# lathe_mainboard.net
KiCad netlist of a schematic drawn in Altium Designer
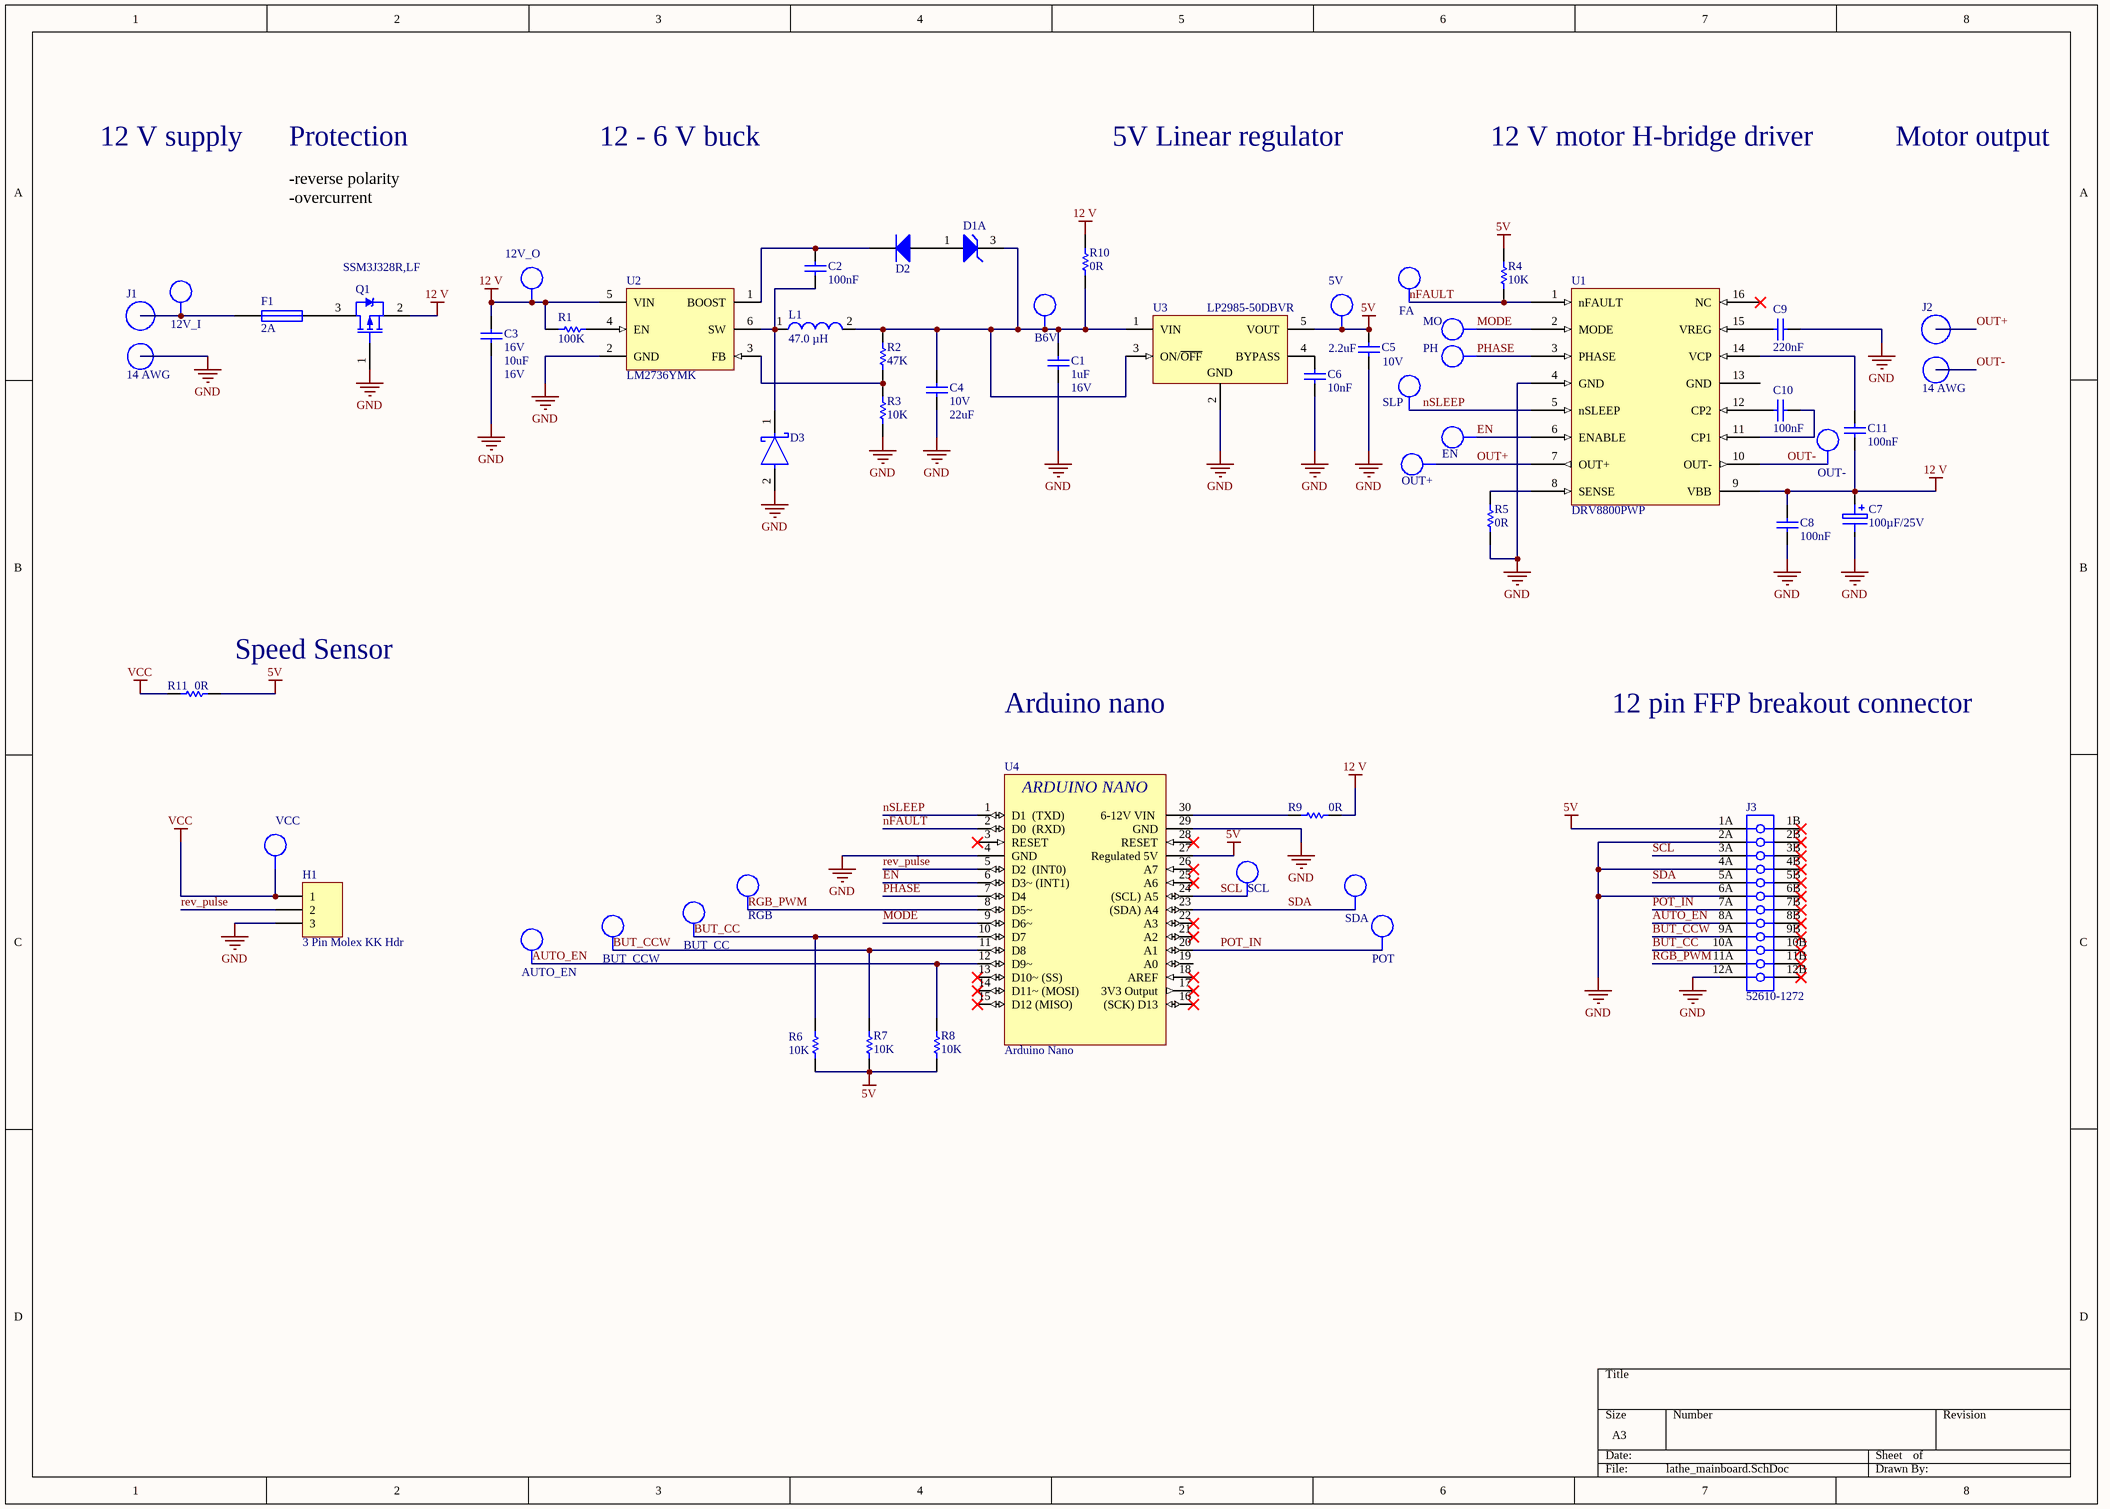
[diagram p0: lathe_mainboard.SchDoc]

(export (version "E")
  (design (tool "Eeschema 10.0.6"))
  (components
    (comp (ref "5V")
      (value "TP")
      (footprint "TP_1206")
      (description "Test-Point 3.3x1.6x2.1mm SMD")
      (fields
        (field (name "MANUFACTURER") "Harwin Inc")
        (field (name "MANUFACTURER PART NUMBER") "S1751-46R")
      )
      (libsource (lib "ECE AD19Components_22V1") (part "TP_1206"))
    )
    (comp (ref "12V_I")
      (value "TP")
      (footprint "TP_1206")
      (description "Test-Point 3.3x1.6x2.1mm SMD")
      (fields
        (field (name "MANUFACTURER") "Harwin Inc")
        (field (name "MANUFACTURER PART NUMBER") "S1751-46R")
      )
      (libsource (lib "ECE AD19Components_22V1") (part "TP_1206"))
    )
    (comp (ref "12V_O")
      (value "TP")
      (footprint "TP_1206")
      (description "Test-Point 3.3x1.6x2.1mm SMD")
      (fields
        (field (name "MANUFACTURER") "Harwin Inc")
        (field (name "MANUFACTURER PART NUMBER") "S1751-46R")
      )
      (libsource (lib "ECE AD19Components_22V1") (part "TP_1206"))
    )
    (comp (ref "AUTO_EN")
      (value "TP")
      (footprint "TP_1206")
      (description "Test-Point 3.3x1.6x2.1mm SMD")
      (fields
        (field (name "MANUFACTURER") "Harwin Inc")
        (field (name "MANUFACTURER PART NUMBER") "S1751-46R")
      )
      (libsource (lib "ECE AD19Components_22V1") (part "TP_1206"))
    )
    (comp (ref "B6V")
      (value "TP")
      (footprint "TP_1206")
      (description "Test-Point 3.3x1.6x2.1mm SMD")
      (fields
        (field (name "MANUFACTURER") "Harwin Inc")
        (field (name "MANUFACTURER PART NUMBER") "S1751-46R")
      )
      (libsource (lib "ECE AD19Components_22V1") (part "TP_1206"))
    )
    (comp (ref "BUT_CC")
      (value "TP")
      (footprint "TP_1206")
      (description "Test-Point 3.3x1.6x2.1mm SMD")
      (fields
        (field (name "MANUFACTURER") "Harwin Inc")
        (field (name "MANUFACTURER PART NUMBER") "S1751-46R")
      )
      (libsource (lib "ECE AD19Components_22V1") (part "TP_1206"))
    )
    (comp (ref "BUT_CCW")
      (value "TP")
      (footprint "TP_1206")
      (description "Test-Point 3.3x1.6x2.1mm SMD")
      (fields
        (field (name "MANUFACTURER") "Harwin Inc")
        (field (name "MANUFACTURER PART NUMBER") "S1751-46R")
      )
      (libsource (lib "ECE AD19Components_22V1") (part "TP_1206"))
    )
    (comp (ref "C1")
      (value "1uF")
      (footprint "CAPC1608L")
      (description "CAP CER 1uF Y5V -20% +80% 16V 0603")
      (fields (field (name "MAX VOLTAGE") "16V"))
      (libsource (lib "ECE AD19Components_22V1") (part "CC_1uF_0603"))
    )
    (comp (ref "C2")
      (value "100nF")
      (footprint "CAPC1608L")
      (description "CAP CER 100nF X7R +-10% 50V 0603")
      (libsource (lib "ECE AD19Components_22V1") (part "CC_100nF_0603"))
    )
    (comp (ref "C3")
      (value "10uF")
      (footprint "CAPC2012L")
      (description "CAP CER 10uF X5R 16V 0805")
      (fields
        (field (name "MANUFACTURER") "Samsung Electro-Mechanics")
        (field (name "MANUFACTURER PART NUMBER") "CL21A106KOQNNWE")
        (field (name "VOLTAGE - RATED") "16V")
        (field (name "MAX VOLTAGE") "16V")
      )
      (libsource (lib "ECE AD19Components_22V1") (part "CC_10uF_0805_16V"))
    )
    (comp (ref "C4")
      (value "22uF")
      (footprint "CAPC3216L")
      (description "CAP CER 22uF Y5V -20% +80% 10V 1206")
      (fields (field (name "MAX VOLTAGE") "10V"))
      (libsource (lib "ECE AD19Components_22V1") (part "CC_22uF_1206"))
    )
    (comp (ref "C5")
      (value "2.2uF")
      (footprint "CAPC1608L")
      (description "CAP CER 2.2uF X5R +-20% 10V 0603")
      (fields (field (name "MAX VOLTAGE") "10V"))
      (libsource (lib "ECE AD19Components_22V1") (part "CC_2.2uF_0603"))
    )
    (comp (ref "C6")
      (value "10nF")
      (footprint "CAPC1608L")
      (description "CAP CER 10nF X7R +-10% 50V 0603")
      (libsource (lib "ECE AD19Components_22V1") (part "CC_10nF_0603"))
    )
    (comp (ref "C7")
      (value "100µF/25V")
      (footprint "CAPAE6666X77M")
      (description "CAP ALUM 100UF 25V 20% SMD")
      (fields
        (field (name "MANUFACTURER") "Nichicon")
        (field (name "MANUFACTURER PART NUMBER") "UWT1E101MCL1GS")
        (field (name "CAPACITANCE") "100µF/25V")
      )
      (libsource (lib "ECE AD19Components_22V1") (part "CA_100uF_25V"))
    )
    (comp (ref "C8")
      (value "100nF")
      (footprint "CAPC1608L")
      (description "CAP CER 100nF X7R +-10% 50V 0603")
      (libsource (lib "ECE AD19Components_22V1") (part "CC_100nF_0603"))
    )
    (comp (ref "C9")
      (value "220nF")
      (footprint "CAPC1608L")
      (description "CAP CER 220nF Y5V -20% +80% 25V 0603")
      (libsource (lib "ECE AD19Components_22V1") (part "CC_220nF_0603"))
    )
    (comp (ref "C10")
      (value "100nF")
      (footprint "CAPC1608L")
      (description "CAP CER 100nF X7R +-10% 50V 0603")
      (libsource (lib "ECE AD19Components_22V1") (part "CC_100nF_0603"))
    )
    (comp (ref "C11")
      (value "100nF")
      (footprint "CAPC1608L")
      (description "CAP CER 100nF X7R +-10% 50V 0603")
      (libsource (lib "ECE AD19Components_22V1") (part "CC_100nF_0603"))
    )
    (comp (ref "D1")
      (value "BZX84C4V3LT1G")
      (footprint "ONSC-SOT-23-3-318-08_V")
      (description "Zener Voltage Regulator, 225 mW, 3-Pin SOT-23, Pb-Free, Tape and Reel")
      (fields (field (name "MANUFACTURER") "On Semiconductor"))
      (libsource (lib "Altium Content Vault") (part "ONSC-A1K3-3"))
    )
    (comp (ref "D2")
      (value "1N4148W-7-F")
      (footprint "DIOD-SOD123-2_V")
      (description "Fast Switching Diode, 100 V, 0.15 A, -65 to 150 degC, 2-Pin?SOD123, RoHS, Tape and Reel")
      (fields (field (name "MANUFACTURER") "DiodesIncorporated"))
      (libsource (lib "Altium Content Vault") (part "D-AK-2"))
    )
    (comp (ref "D3")
      (value "MSS1P3L-M3/89A")
      (footprint "FP-96591-MFG")
      (description "DIODE SCHOTTKY 30V 1A MICROSMP")
      (fields
        (field (name "OCTOPART") "https://octopart.com/mss1p3l-m3%2F89a-vishay-42670898")
        (field (name "MANUFACTURER") "Vishay")
      )
      (libsource (lib "Altium Content Vault") (part "1d6ec82d83fb6aee721767c19dac4b9"))
    )
    (comp (ref "EN")
      (value "TP")
      (footprint "TP_1206")
      (description "Test-Point 3.3x1.6x2.1mm SMD")
      (fields
        (field (name "MANUFACTURER") "Harwin Inc")
        (field (name "MANUFACTURER PART NUMBER") "S1751-46R")
      )
      (libsource (lib "ECE AD19Components_22V1") (part "TP_1206"))
    )
    (comp (ref "F1")
      (value "2A")
      (footprint "RESC3216N")
      (description "Fuse 2.0A Very Fast Acting 1206 SMD")
      (fields
        (field (name "MANUFACTURER") "MULTICOMP")
        (field (name "MANUFACTURER PART NUMBER") "MC12CF 002")
      )
      (libsource (lib "ECE AD19Components_22V1") (part "FS_Fuse_2.0A"))
    )
    (comp (ref "FA")
      (value "TP")
      (footprint "TP_1206")
      (description "Test-Point 3.3x1.6x2.1mm SMD")
      (fields
        (field (name "MANUFACTURER") "Harwin Inc")
        (field (name "MANUFACTURER PART NUMBER") "S1751-46R")
      )
      (libsource (lib "ECE AD19Components_22V1") (part "TP_1206"))
    )
    (comp (ref "H1")
      (value "3 Pin Molex KK Hdr")
      (footprint "MOLEX_KK_3_HDR")
      (description "CONN HEADER 3POS 2.54mm VERT_Thru Hole")
      (fields (field (name "MANUFACTURER") "Molex"))
      (libsource (lib "ECE AD19Components_22V1") (part "JA_MOLEX_KK_3POS"))
    )
    (comp (ref "J1")
      (value "14 AWG")
      (footprint "14AWG_holes")
      (libsource (lib "lathe_library") (part "14AWG_holle"))
    )
    (comp (ref "J2")
      (value "14 AWG")
      (footprint "14AWG_holes")
      (libsource (lib "lathe_library") (part "14AWG_holle"))
    )
    (comp (ref "J3")
      (value "52610-1272")
      (footprint "MOLX-52610-1272")
      (fields (field (name "MANUFACTURER") "Molex"))
      (libsource (lib "Altium Content Vault") (part "MOLX-52610-1272"))
    )
    (comp (ref "L1")
      (value "47.0 µH")
      (footprint "WE-PD-L")
      (description "SMD-Shielded Power Inductor WE-PD, L = 47.0 µH")
      (libsource (lib "Altium Content Vault") (part "PAS-IND-INDUCTOR-2"))
    )
    (comp (ref "MO")
      (value "TP")
      (footprint "TP_1206")
      (description "Test-Point 3.3x1.6x2.1mm SMD")
      (fields
        (field (name "MANUFACTURER") "Harwin Inc")
        (field (name "MANUFACTURER PART NUMBER") "S1751-46R")
      )
      (libsource (lib "ECE AD19Components_22V1") (part "TP_1206"))
    )
    (comp (ref "OUT+")
      (value "TP")
      (footprint "TP_1206")
      (description "Test-Point 3.3x1.6x2.1mm SMD")
      (fields
        (field (name "MANUFACTURER") "Harwin Inc")
        (field (name "MANUFACTURER PART NUMBER") "S1751-46R")
      )
      (libsource (lib "ECE AD19Components_22V1") (part "TP_1206"))
    )
    (comp (ref "OUT-")
      (value "TP")
      (footprint "TP_1206")
      (description "Test-Point 3.3x1.6x2.1mm SMD")
      (fields
        (field (name "MANUFACTURER") "Harwin Inc")
        (field (name "MANUFACTURER PART NUMBER") "S1751-46R")
      )
      (libsource (lib "ECE AD19Components_22V1") (part "TP_1206"))
    )
    (comp (ref "PH")
      (value "TP")
      (footprint "TP_1206")
      (description "Test-Point 3.3x1.6x2.1mm SMD")
      (fields
        (field (name "MANUFACTURER") "Harwin Inc")
        (field (name "MANUFACTURER PART NUMBER") "S1751-46R")
      )
      (libsource (lib "ECE AD19Components_22V1") (part "TP_1206"))
    )
    (comp (ref "POT")
      (value "TP")
      (footprint "TP_1206")
      (description "Test-Point 3.3x1.6x2.1mm SMD")
      (fields
        (field (name "MANUFACTURER") "Harwin Inc")
        (field (name "MANUFACTURER PART NUMBER") "S1751-46R")
      )
      (libsource (lib "ECE AD19Components_22V1") (part "TP_1206"))
    )
    (comp (ref "Q1")
      (value "SSM3J328R,LF")
      (footprint "SOT23_L")
      (description "MOSFET P-CH 20V 6A SOT23-3")
      (fields
        (field (name "MANUFACTURER") "Toshiba")
        (field (name "MANUFACTURER PART NUMBER") "SSM3J328R,LF")
      )
      (libsource (lib "ECE AD19Components_22V1") (part "TM_SSM3J328R"))
    )
    (comp (ref "R1")
      (value "100K")
      (footprint "RESC1608L")
      (description "RES 100K OHM 1/10W 5% 0603 SMD")
      (libsource (lib "ECE AD19Components_22V1") (part "RS_100K"))
    )
    (comp (ref "R2")
      (value "47K")
      (footprint "RESC1608N")
      (description "RES 47.0K OHM 1/10W 5% 0603 SMD")
      (libsource (lib "ECE AD19Components_22V1") (part "RS_47K"))
    )
    (comp (ref "R3")
      (value "10K")
      (footprint "RESC1608L")
      (description "RES 10.0K OHM 1/10W 5% 0603 SMD")
      (libsource (lib "ECE AD19Components_22V1") (part "RS_10K"))
    )
    (comp (ref "R4")
      (value "10K")
      (footprint "RESC1608L")
      (description "RES 10.0K OHM 1/10W 5% 0603 SMD")
      (libsource (lib "ECE AD19Components_22V1") (part "RS_10K"))
    )
    (comp (ref "R5")
      (value "0R")
      (footprint "RESC1608L")
      (description "RES 0.0 OHM 1/10W 5% 0603 SMD")
      (libsource (lib "ECE AD19Components_22V1") (part "RS_0R0"))
    )
    (comp (ref "R6")
      (value "10K")
      (footprint "RESC1608L")
      (description "RES 10.0K OHM 1/10W 5% 0603 SMD")
      (libsource (lib "ECE AD19Components_22V1") (part "RS_10K"))
    )
    (comp (ref "R7")
      (value "10K")
      (footprint "RESC1608L")
      (description "RES 10.0K OHM 1/10W 5% 0603 SMD")
      (libsource (lib "ECE AD19Components_22V1") (part "RS_10K"))
    )
    (comp (ref "R8")
      (value "10K")
      (footprint "RESC1608L")
      (description "RES 10.0K OHM 1/10W 5% 0603 SMD")
      (libsource (lib "ECE AD19Components_22V1") (part "RS_10K"))
    )
    (comp (ref "R9")
      (value "0R")
      (footprint "RESC1608L")
      (description "RES 0.0 OHM 1/10W 5% 0603 SMD")
      (libsource (lib "ECE AD19Components_22V1") (part "RS_0R0"))
    )
    (comp (ref "R10")
      (value "0R")
      (footprint "RESC1608L")
      (description "RES 0.0 OHM 1/10W 5% 0603 SMD")
      (libsource (lib "ECE AD19Components_22V1") (part "RS_0R0"))
    )
    (comp (ref "R11")
      (value "0R")
      (footprint "RESC1608L")
      (description "RES 0.0 OHM 1/10W 5% 0603 SMD")
      (libsource (lib "ECE AD19Components_22V1") (part "RS_0R0"))
    )
    (comp (ref "RGB")
      (value "TP")
      (footprint "TP_1206")
      (description "Test-Point 3.3x1.6x2.1mm SMD")
      (fields
        (field (name "MANUFACTURER") "Harwin Inc")
        (field (name "MANUFACTURER PART NUMBER") "S1751-46R")
      )
      (libsource (lib "ECE AD19Components_22V1") (part "TP_1206"))
    )
    (comp (ref "SCL")
      (value "TP")
      (footprint "TP_1206")
      (description "Test-Point 3.3x1.6x2.1mm SMD")
      (fields
        (field (name "MANUFACTURER") "Harwin Inc")
        (field (name "MANUFACTURER PART NUMBER") "S1751-46R")
      )
      (libsource (lib "ECE AD19Components_22V1") (part "TP_1206"))
    )
    (comp (ref "SDA")
      (value "TP")
      (footprint "TP_1206")
      (description "Test-Point 3.3x1.6x2.1mm SMD")
      (fields
        (field (name "MANUFACTURER") "Harwin Inc")
        (field (name "MANUFACTURER PART NUMBER") "S1751-46R")
      )
      (libsource (lib "ECE AD19Components_22V1") (part "TP_1206"))
    )
    (comp (ref "SLP")
      (value "TP")
      (footprint "TP_1206")
      (description "Test-Point 3.3x1.6x2.1mm SMD")
      (fields
        (field (name "MANUFACTURER") "Harwin Inc")
        (field (name "MANUFACTURER PART NUMBER") "S1751-46R")
      )
      (libsource (lib "ECE AD19Components_22V1") (part "TP_1206"))
    )
    (comp (ref "U1")
      (value "DRV8800PWP")
      (footprint "SOP65P640X120-17N")
      (description "IC MTR DRV BIPOLR 8-38V 16HTSSOP")
      (libsource (lib "lathe_library") (part "DRV8800PWP"))
    )
    (comp (ref "U2")
      (value "LM2736YMK")
      (footprint "DDC0006A_L")
      (description "750mA Load Step-Down DC-DC Regulator, 6-pin Tiny SOT23")
      (fields (field (name "MANUFACTURER") "Texas Instruments"))
      (libsource (lib "Altium Content Vault") (part "PM-DCDC-LM2736MK"))
    )
    (comp (ref "U3")
      (value "LP2985-50DBVR")
      (footprint "DBV0005A_M")
      (fields (field (name "MANUFACTURER") "Texas Instruments"))
      (libsource (lib "lathe_library") (part "LP2985-50DBVR"))
    )
    (comp (ref "U4")
      (value "Arduino Nano")
      (footprint "Arduino-nano")
      (libsource (lib "ECE AD19Components_22V1") (part "Arduino Nano"))
    )
    (comp (ref "VCC")
      (value "TP")
      (footprint "TP_1206")
      (description "Test-Point 3.3x1.6x2.1mm SMD")
      (fields
        (field (name "MANUFACTURER") "Harwin Inc")
        (field (name "MANUFACTURER PART NUMBER") "S1751-46R")
      )
      (libsource (lib "ECE AD19Components_22V1") (part "TP_1206"))
    )
  )
  (nets
    (net (code "1") (name "/AUTO_EN") (class "Default")
      (node (ref "AUTO_EN") (pin "1") (pinfunction "1_1") (pintype "passive"))
      (node (ref "J3") (pin "8A") (pinfunction "8A_8A") (pintype "passive"))
      (node (ref "R8") (pin "2") (pinfunction "2_2") (pintype "passive"))
      (node (ref "U4") (pin "12") (pinfunction "D9~_12") (pintype "bidirectional"))
    )
    (net (code "2") (name "/BUT_CC") (class "Default")
      (node (ref "BUT_CC") (pin "1") (pinfunction "1_1") (pintype "passive"))
      (node (ref "J3") (pin "10A") (pinfunction "10A_10A") (pintype "passive"))
      (node (ref "R6") (pin "2") (pinfunction "2_2") (pintype "passive"))
      (node (ref "U4") (pin "10") (pinfunction "D7_10") (pintype "bidirectional"))
    )
    (net (code "3") (name "/BUT_CCW") (class "Default")
      (node (ref "BUT_CCW") (pin "1") (pinfunction "1_1") (pintype "passive"))
      (node (ref "J3") (pin "9A") (pinfunction "9A_9A") (pintype "passive"))
      (node (ref "R7") (pin "2") (pinfunction "2_2") (pintype "passive"))
      (node (ref "U4") (pin "11") (pinfunction "D8_11") (pintype "bidirectional"))
    )
    (net (code "4") (name "/EN") (class "Default")
      (node (ref "EN") (pin "1") (pinfunction "1_1") (pintype "passive"))
      (node (ref "U1") (pin "6") (pinfunction "ENABLE_6") (pintype "input"))
      (node (ref "U4") (pin "6") (pinfunction "D3~_(INT1)_6") (pintype "bidirectional"))
    )
    (net (code "5") (name "/MODE") (class "Default")
      (node (ref "MO") (pin "1") (pinfunction "1_1") (pintype "passive"))
      (node (ref "U1") (pin "2") (pinfunction "MODE_2") (pintype "input"))
      (node (ref "U4") (pin "9") (pinfunction "D6~_9") (pintype "bidirectional"))
    )
    (net (code "6") (name "/OUT+") (class "Default")
      (node (ref "J2") (pin "1") (pinfunction "1_1") (pintype "passive"))
      (node (ref "OUT+") (pin "1") (pinfunction "1_1") (pintype "passive"))
      (node (ref "U1") (pin "7") (pinfunction "OUT+_7") (pintype "output"))
    )
    (net (code "7") (name "/OUT-") (class "Default")
      (node (ref "J2") (pin "2") (pinfunction "2_2") (pintype "passive"))
      (node (ref "OUT-") (pin "1") (pinfunction "1_1") (pintype "passive"))
      (node (ref "U1") (pin "10") (pinfunction "OUT-_10") (pintype "output"))
    )
    (net (code "8") (name "/PHASE") (class "Default")
      (node (ref "PH") (pin "1") (pinfunction "1_1") (pintype "passive"))
      (node (ref "U1") (pin "3") (pinfunction "PHASE_3") (pintype "input"))
      (node (ref "U4") (pin "7") (pinfunction "D4_7") (pintype "bidirectional"))
    )
    (net (code "9") (name "/POT_IN") (class "Default")
      (node (ref "J3") (pin "7A") (pinfunction "7A_7A") (pintype "passive"))
      (node (ref "POT") (pin "1") (pinfunction "1_1") (pintype "passive"))
      (node (ref "U4") (pin "20") (pinfunction "A1_20") (pintype "bidirectional"))
    )
    (net (code "10") (name "/RGB_PWM") (class "Default")
      (node (ref "J3") (pin "11A") (pinfunction "11A_11A") (pintype "passive"))
      (node (ref "RGB") (pin "1") (pinfunction "1_1") (pintype "passive"))
      (node (ref "U4") (pin "8") (pinfunction "D5~_8") (pintype "bidirectional"))
    )
    (net (code "11") (name "/SCL") (class "Default")
      (node (ref "J3") (pin "3A") (pinfunction "3A_3A") (pintype "passive"))
      (node (ref "SCL") (pin "1") (pinfunction "1_1") (pintype "passive"))
      (node (ref "U4") (pin "24") (pinfunction "(SCL)_A5_24") (pintype "bidirectional"))
    )
    (net (code "12") (name "/SDA") (class "Default")
      (node (ref "J3") (pin "5A") (pinfunction "5A_5A") (pintype "passive"))
      (node (ref "SDA") (pin "1") (pinfunction "1_1") (pintype "passive"))
      (node (ref "U4") (pin "23") (pinfunction "(SDA)_A4_23") (pintype "bidirectional"))
    )
    (net (code "13") (name "/nFAULT") (class "Default")
      (node (ref "FA") (pin "1") (pinfunction "1_1") (pintype "passive"))
      (node (ref "R4") (pin "1") (pinfunction "1_1") (pintype "passive"))
      (node (ref "U1") (pin "1") (pinfunction "nFAULT_1") (pintype "input"))
      (node (ref "U4") (pin "2") (pinfunction "D0__(RXD)_2") (pintype "bidirectional"))
    )
    (net (code "14") (name "/nSLEEP") (class "Default")
      (node (ref "SLP") (pin "1") (pinfunction "1_1") (pintype "passive"))
      (node (ref "U1") (pin "5") (pinfunction "nSLEEP_5") (pintype "input"))
      (node (ref "U4") (pin "1") (pinfunction "D1__(TXD)_1") (pintype "bidirectional"))
    )
    (net (code "15") (name "/rev_pulse") (class "Default")
      (node (ref "H1") (pin "2") (pinfunction "2_2") (pintype "passive"))
      (node (ref "U4") (pin "5") (pinfunction "D2__(INT0)_5") (pintype "bidirectional"))
    )
    (net (code "16") (name "5V") (class "Default")
      (node (ref "5V") (pin "1") (pinfunction "1_1") (pintype "passive"))
      (node (ref "C5") (pin "2") (pinfunction "2_2") (pintype "passive"))
      (node (ref "J3") (pin "1A") (pinfunction "1A_1A") (pintype "passive"))
      (node (ref "R11") (pin "2") (pinfunction "2_2") (pintype "passive"))
      (node (ref "R4") (pin "2") (pinfunction "2_2") (pintype "passive"))
      (node (ref "R6") (pin "1") (pinfunction "1_1") (pintype "passive"))
      (node (ref "R7") (pin "1") (pinfunction "1_1") (pintype "passive"))
      (node (ref "R8") (pin "1") (pinfunction "1_1") (pintype "passive"))
      (node (ref "U3") (pin "5") (pinfunction "VOUT_5") (pintype "power_in"))
      (node (ref "U4") (pin "27") (pinfunction "Regulated_5V_27") (pintype "power_in"))
    )
    (net (code "17") (name "12 V") (class "Default")
      (node (ref "12V_O") (pin "1") (pinfunction "1_1") (pintype "passive"))
      (node (ref "C11") (pin "1") (pinfunction "1_1") (pintype "passive"))
      (node (ref "C3") (pin "2") (pinfunction "2_2") (pintype "passive"))
      (node (ref "C7") (pin "2") (pintype "passive"))
      (node (ref "C8") (pin "2") (pinfunction "2_2") (pintype "passive"))
      (node (ref "Q1") (pin "2") (pinfunction "2_2") (pintype "passive"))
      (node (ref "R1") (pin "2") (pinfunction "2_2") (pintype "passive"))
      (node (ref "R10") (pin "2") (pinfunction "2_2") (pintype "passive"))
      (node (ref "R9") (pin "2") (pinfunction "2_2") (pintype "passive"))
      (node (ref "U1") (pin "9") (pinfunction "VBB_9") (pintype "power_in"))
      (node (ref "U2") (pin "5") (pinfunction "VIN_5") (pintype "power_in"))
    )
    (net (code "18") (name "GND") (class "Default")
      (node (ref "C1") (pin "1") (pinfunction "1_1") (pintype "passive"))
      (node (ref "C3") (pin "1") (pinfunction "1_1") (pintype "passive"))
      (node (ref "C4") (pin "1") (pinfunction "1_1") (pintype "passive"))
      (node (ref "C5") (pin "1") (pinfunction "1_1") (pintype "passive"))
      (node (ref "C6") (pin "1") (pinfunction "1_1") (pintype "passive"))
      (node (ref "C7") (pin "1") (pintype "passive"))
      (node (ref "C8") (pin "1") (pinfunction "1_1") (pintype "passive"))
      (node (ref "C9") (pin "2") (pinfunction "2_2") (pintype "passive"))
      (node (ref "D3") (pin "2") (pinfunction "A_2") (pintype "passive"))
      (node (ref "H1") (pin "3") (pinfunction "3_3") (pintype "passive"))
      (node (ref "J1") (pin "2") (pinfunction "2_2") (pintype "passive"))
      (node (ref "J3") (pin "12A") (pinfunction "12A_12A") (pintype "passive"))
      (node (ref "J3") (pin "2A") (pinfunction "2A_2A") (pintype "passive"))
      (node (ref "J3") (pin "4A") (pinfunction "4A_4A") (pintype "passive"))
      (node (ref "J3") (pin "6A") (pinfunction "6A_6A") (pintype "passive"))
      (node (ref "Q1") (pin "1") (pinfunction "1_1") (pintype "passive"))
      (node (ref "R3") (pin "1") (pinfunction "1_1") (pintype "passive"))
      (node (ref "R5") (pin "1") (pinfunction "1_1") (pintype "passive"))
      (node (ref "U1") (pin "4") (pinfunction "GND_4") (pintype "input"))
      (node (ref "U2") (pin "2") (pinfunction "GND_2") (pintype "power_in"))
      (node (ref "U3") (pin "2") (pinfunction "GND_2") (pintype "power_in"))
      (node (ref "U4") (pin "29") (pinfunction "GND_29") (pintype "power_in"))
      (node (ref "U4") (pin "4") (pinfunction "GND_4") (pintype "power_in"))
    )
    (net (code "19") (name "Net-(12V_I-Pad1)") (class "Default")
      (node (ref "12V_I") (pin "1") (pinfunction "1_1") (pintype "passive"))
      (node (ref "F1") (pin "1") (pinfunction "1_1") (pintype "passive"))
      (node (ref "J1") (pin "1") (pinfunction "1_1") (pintype "passive"))
    )
    (net (code "20") (name "Net-(D1A-A)") (class "Default")
      (node (ref "D1") (pin "1") (pinfunction "A_1") (pintype "passive"))
      (node (ref "D2") (pin "1") (pinfunction "A_1") (pintype "passive"))
    )
    (net (code "21") (name "Net-(D1A-K)") (class "Default")
      (node (ref "B6V") (pin "1") (pinfunction "1_1") (pintype "passive"))
      (node (ref "C1") (pin "2") (pinfunction "2_2") (pintype "passive"))
      (node (ref "C4") (pin "2") (pinfunction "2_2") (pintype "passive"))
      (node (ref "D1") (pin "3") (pinfunction "K_3") (pintype "passive"))
      (node (ref "L1") (pin "2") (pinfunction "2_2") (pintype "passive"))
      (node (ref "R10") (pin "1") (pinfunction "1_1") (pintype "passive"))
      (node (ref "R2") (pin "2") (pinfunction "2_2") (pintype "passive"))
      (node (ref "U3") (pin "1") (pinfunction "VIN_1") (pintype "power_in"))
      (node (ref "U3") (pin "3") (pinfunction "ON/~{OFF}_3") (pintype "input"))
    )
    (net (code "22") (name "Net-(D2-K)") (class "Default")
      (node (ref "C2") (pin "1") (pinfunction "1_1") (pintype "passive"))
      (node (ref "D2") (pin "2") (pinfunction "K_2") (pintype "passive"))
      (node (ref "U2") (pin "1") (pinfunction "BOOST_1") (pintype "passive"))
    )
    (net (code "23") (name "Net-(D3-C)") (class "Default")
      (node (ref "C2") (pin "2") (pinfunction "2_2") (pintype "passive"))
      (node (ref "D3") (pin "1") (pinfunction "C_1") (pintype "passive"))
      (node (ref "L1") (pin "1") (pinfunction "1_1") (pintype "passive"))
      (node (ref "U2") (pin "6") (pinfunction "SW_6") (pintype "power_in"))
    )
    (net (code "24") (name "Net-(F1-Pad2)") (class "Default")
      (node (ref "F1") (pin "2") (pinfunction "2_2") (pintype "passive"))
      (node (ref "Q1") (pin "3") (pinfunction "3_3") (pintype "passive"))
    )
    (net (code "25") (name "Net-(U1-CP1)") (class "Default")
      (node (ref "C10") (pin "1") (pinfunction "1_1") (pintype "passive"))
      (node (ref "U1") (pin "11") (pinfunction "CP1_11") (pintype "input"))
    )
    (net (code "26") (name "Net-(U1-CP2)") (class "Default")
      (node (ref "C10") (pin "2") (pinfunction "2_2") (pintype "passive"))
      (node (ref "U1") (pin "12") (pinfunction "CP2_12") (pintype "input"))
    )
    (net (code "27") (name "Net-(U1-SENSE)") (class "Default")
      (node (ref "R5") (pin "2") (pinfunction "2_2") (pintype "passive"))
      (node (ref "U1") (pin "8") (pinfunction "SENSE_8") (pintype "input"))
    )
    (net (code "28") (name "Net-(U1-VCP)") (class "Default")
      (node (ref "C11") (pin "2") (pinfunction "2_2") (pintype "passive"))
      (node (ref "U1") (pin "14") (pinfunction "VCP_14") (pintype "input"))
    )
    (net (code "29") (name "Net-(U1-VREG)") (class "Default")
      (node (ref "C9") (pin "1") (pinfunction "1_1") (pintype "passive"))
      (node (ref "U1") (pin "15") (pinfunction "VREG_15") (pintype "input"))
    )
    (net (code "30") (name "Net-(U2-EN)") (class "Default")
      (node (ref "R1") (pin "1") (pinfunction "1_1") (pintype "passive"))
      (node (ref "U2") (pin "4") (pinfunction "EN_4") (pintype "input"))
    )
    (net (code "31") (name "Net-(U2-FB)") (class "Default")
      (node (ref "R2") (pin "1") (pinfunction "1_1") (pintype "passive"))
      (node (ref "R3") (pin "2") (pinfunction "2_2") (pintype "passive"))
      (node (ref "U2") (pin "3") (pinfunction "FB_3") (pintype "input"))
    )
    (net (code "32") (name "Net-(U3-BYPASS)") (class "Default")
      (node (ref "C6") (pin "2") (pinfunction "2_2") (pintype "passive"))
      (node (ref "U3") (pin "4") (pinfunction "BYPASS_4") (pintype "passive"))
    )
    (net (code "33") (name "Net-(U4-6-12V_VIN)") (class "Default")
      (node (ref "R9") (pin "1") (pinfunction "1_1") (pintype "passive"))
      (node (ref "U4") (pin "30") (pinfunction "6-12V_VIN_30") (pintype "power_in"))
    )
    (net (code "34") (name "VCC") (class "Default")
      (node (ref "H1") (pin "1") (pinfunction "1_1") (pintype "passive"))
      (node (ref "R11") (pin "1") (pinfunction "1_1") (pintype "passive"))
      (node (ref "VCC") (pin "1") (pinfunction "1_1") (pintype "passive"))
    )
    (net (code "35") (name "unconnected-(J3-Pad1B)") (class "Default")
      (node (ref "J3") (pin "1B") (pinfunction "1B_1B") (pintype "passive+no_connect"))
    )
    (net (code "36") (name "unconnected-(J3-Pad2B)") (class "Default")
      (node (ref "J3") (pin "2B") (pinfunction "2B_2B") (pintype "passive+no_connect"))
    )
    (net (code "37") (name "unconnected-(J3-Pad3B)") (class "Default")
      (node (ref "J3") (pin "3B") (pinfunction "3B_3B") (pintype "passive+no_connect"))
    )
    (net (code "38") (name "unconnected-(J3-Pad4B)") (class "Default")
      (node (ref "J3") (pin "4B") (pinfunction "4B_4B") (pintype "passive+no_connect"))
    )
    (net (code "39") (name "unconnected-(J3-Pad5B)") (class "Default")
      (node (ref "J3") (pin "5B") (pinfunction "5B_5B") (pintype "passive+no_connect"))
    )
    (net (code "40") (name "unconnected-(J3-Pad6B)") (class "Default")
      (node (ref "J3") (pin "6B") (pinfunction "6B_6B") (pintype "passive+no_connect"))
    )
    (net (code "41") (name "unconnected-(J3-Pad7B)") (class "Default")
      (node (ref "J3") (pin "7B") (pinfunction "7B_7B") (pintype "passive+no_connect"))
    )
    (net (code "42") (name "unconnected-(J3-Pad8B)") (class "Default")
      (node (ref "J3") (pin "8B") (pinfunction "8B_8B") (pintype "passive+no_connect"))
    )
    (net (code "43") (name "unconnected-(J3-Pad9B)") (class "Default")
      (node (ref "J3") (pin "9B") (pinfunction "9B_9B") (pintype "passive+no_connect"))
    )
    (net (code "44") (name "unconnected-(J3-Pad10B)") (class "Default")
      (node (ref "J3") (pin "10B") (pinfunction "10B_10B") (pintype "passive+no_connect"))
    )
    (net (code "45") (name "unconnected-(J3-Pad11B)") (class "Default")
      (node (ref "J3") (pin "11B") (pinfunction "11B_11B") (pintype "passive+no_connect"))
    )
    (net (code "46") (name "unconnected-(J3-Pad12B)") (class "Default")
      (node (ref "J3") (pin "12B") (pinfunction "12B_12B") (pintype "passive+no_connect"))
    )
    (net (code "47") (name "unconnected-(U1-GND-Pad13)") (class "Default")
      (node (ref "U1") (pin "13") (pinfunction "GND_13") (pintype "power_in"))
    )
    (net (code "48") (name "unconnected-(U1-NC-Pad16)") (class "Default")
      (node (ref "U1") (pin "16") (pinfunction "NC_16") (pintype "input+no_connect"))
    )
    (net (code "49") (name "unconnected-(U4-(SCK)_D13-Pad16)") (class "Default")
      (node (ref "U4") (pin "16") (pinfunction "(SCK)_D13_16") (pintype "bidirectional+no_connect"))
    )
    (net (code "50") (name "unconnected-(U4-3V3_Output-Pad17)") (class "Default")
      (node (ref "U4") (pin "17") (pinfunction "3V3_Output_17") (pintype "output+no_connect"))
    )
    (net (code "51") (name "unconnected-(U4-A0-Pad19)") (class "Default")
      (node (ref "U4") (pin "19") (pinfunction "A0_19") (pintype "bidirectional"))
    )
    (net (code "52") (name "unconnected-(U4-A2-Pad21)") (class "Default")
      (node (ref "U4") (pin "21") (pinfunction "A2_21") (pintype "bidirectional+no_connect"))
    )
    (net (code "53") (name "unconnected-(U4-A3-Pad22)") (class "Default")
      (node (ref "U4") (pin "22") (pinfunction "A3_22") (pintype "bidirectional+no_connect"))
    )
    (net (code "54") (name "unconnected-(U4-A6-Pad25)") (class "Default")
      (node (ref "U4") (pin "25") (pinfunction "A6_25") (pintype "input+no_connect"))
    )
    (net (code "55") (name "unconnected-(U4-A7-Pad26)") (class "Default")
      (node (ref "U4") (pin "26") (pinfunction "A7_26") (pintype "input+no_connect"))
    )
    (net (code "56") (name "unconnected-(U4-AREF-Pad18)") (class "Default")
      (node (ref "U4") (pin "18") (pinfunction "AREF_18") (pintype "input+no_connect"))
    )
    (net (code "57") (name "unconnected-(U4-D10~_(SS)-Pad13)") (class "Default")
      (node (ref "U4") (pin "13") (pinfunction "D10~_(SS)_13") (pintype "bidirectional+no_connect"))
    )
    (net (code "58") (name "unconnected-(U4-D11~_(MOSI)-Pad14)") (class "Default")
      (node (ref "U4") (pin "14") (pinfunction "D11~_(MOSI)_14") (pintype "bidirectional+no_connect"))
    )
    (net (code "59") (name "unconnected-(U4-D12_(MISO)-Pad15)") (class "Default")
      (node (ref "U4") (pin "15") (pinfunction "D12_(MISO)_15") (pintype "bidirectional+no_connect"))
    )
    (net (code "60") (name "unconnected-(U4-RESET-Pad3)") (class "Default")
      (node (ref "U4") (pin "3") (pinfunction "RESET_3") (pintype "input+no_connect"))
    )
    (net (code "61") (name "unconnected-(U4-RESET-Pad28)") (class "Default")
      (node (ref "U4") (pin "28") (pinfunction "RESET_28") (pintype "input+no_connect"))
    )
  )
)
